# HITOMI.net
KiCad netlist of a schematic drawn in EAGLE
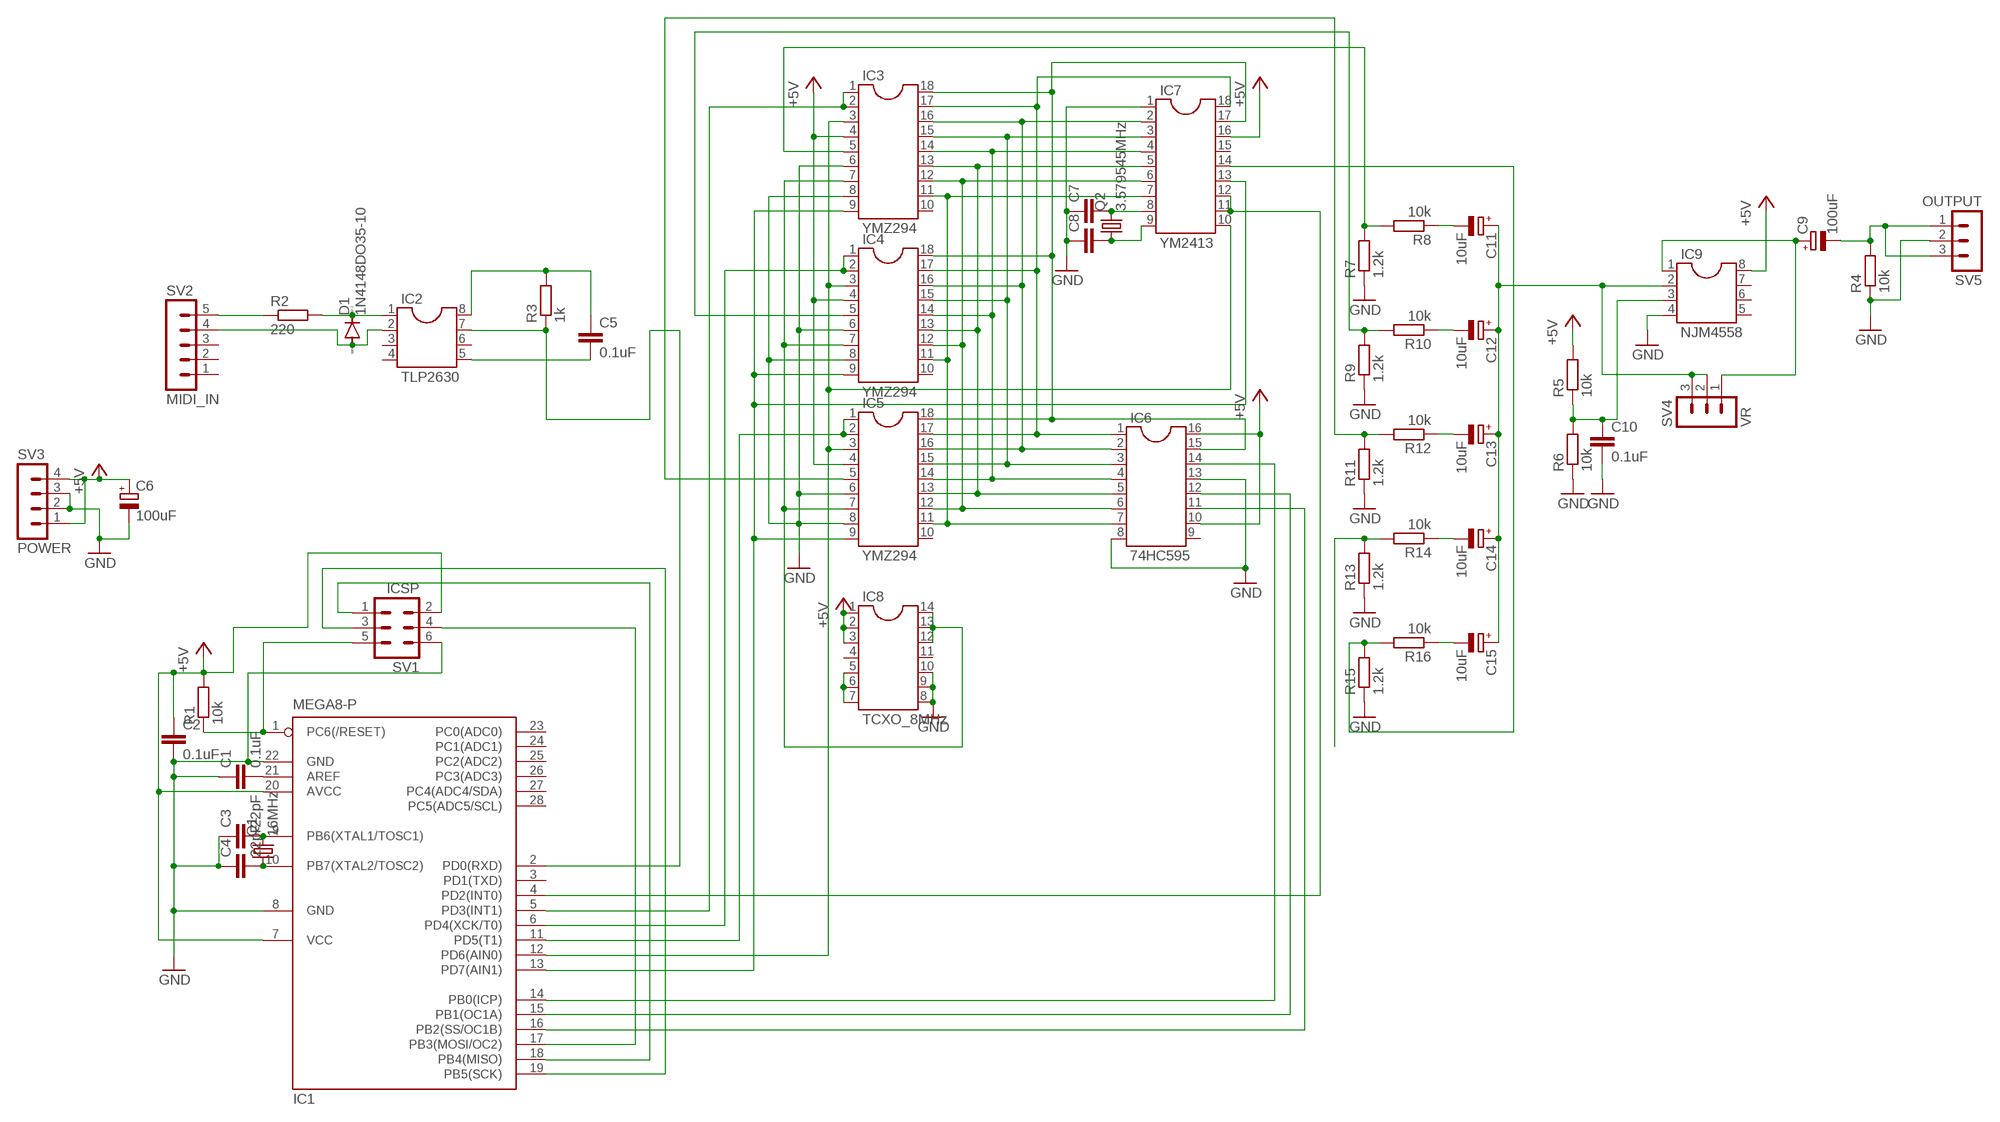
[diagram p0: schematic, sheet 1]

(export (version "E")
  (design (tool "Eeschema 10.0.6"))
  (components
    (comp (ref "C1")
      (value "0.1uF")
      (footprint "eagle-import:C050-025X075")
      (libsource (lib "eagle-import") (part "C-EU050-025X075"))
    )
    (comp (ref "C2")
      (value "0.1uF")
      (footprint "eagle-import:C050-025X075")
      (libsource (lib "eagle-import") (part "C-EU050-025X075"))
    )
    (comp (ref "C3")
      (value "22pF")
      (footprint "eagle-import:C050-025X075")
      (libsource (lib "eagle-import") (part "C-EU050-025X075"))
    )
    (comp (ref "C4")
      (value "22pF")
      (footprint "eagle-import:C050-025X075")
      (libsource (lib "eagle-import") (part "C-EU050-025X075"))
    )
    (comp (ref "C5")
      (value "0.1uF")
      (footprint "eagle-import:C050-025X075")
      (libsource (lib "eagle-import") (part "C-EU050-025X075"))
    )
    (comp (ref "C6")
      (value "100uF")
      (footprint "eagle-import:E2,5-7")
      (libsource (lib "eagle-import") (part "CPOL-EUE2.5-7"))
    )
    (comp (ref "C7")
      (value "C-EU050-025X075")
      (footprint "eagle-import:C050-025X075")
      (libsource (lib "eagle-import") (part "C-EU050-025X075"))
    )
    (comp (ref "C8")
      (value "C-EU050-025X075")
      (footprint "eagle-import:C050-025X075")
      (libsource (lib "eagle-import") (part "C-EU050-025X075"))
    )
    (comp (ref "C9")
      (value "100uF")
      (footprint "eagle-import:E2,5-7")
      (libsource (lib "eagle-import") (part "CPOL-EUE2.5-7"))
    )
    (comp (ref "C10")
      (value "0.1uF")
      (footprint "eagle-import:C050-025X075")
      (libsource (lib "eagle-import") (part "C-EU050-025X075"))
    )
    (comp (ref "C11")
      (value "10uF")
      (footprint "eagle-import:E2,5-7")
      (libsource (lib "eagle-import") (part "CPOL-EUE2.5-7"))
    )
    (comp (ref "C12")
      (value "10uF")
      (footprint "eagle-import:E2,5-7")
      (libsource (lib "eagle-import") (part "CPOL-EUE2.5-7"))
    )
    (comp (ref "C13")
      (value "10uF")
      (footprint "eagle-import:E2,5-7")
      (libsource (lib "eagle-import") (part "CPOL-EUE2.5-7"))
    )
    (comp (ref "C14")
      (value "10uF")
      (footprint "eagle-import:E2,5-7")
      (libsource (lib "eagle-import") (part "CPOL-EUE2.5-7"))
    )
    (comp (ref "C15")
      (value "10uF")
      (footprint "eagle-import:E2,5-7")
      (libsource (lib "eagle-import") (part "CPOL-EUE2.5-7"))
    )
    (comp (ref "D1")
      (value "1N4148DO35-10")
      (footprint "eagle-import:DO35-10")
      (libsource (lib "eagle-import") (part "1N4148DO35-10"))
    )
    (comp (ref "IC1")
      (value "MEGA8-P")
      (footprint "eagle-import:DIL28-3")
      (libsource (lib "eagle-import") (part "MEGA8-P"))
    )
    (comp (ref "IC2")
      (value "TLP2630")
      (footprint "eagle-import:DIL08")
      (libsource (lib "eagle-import") (part "DIL8"))
    )
    (comp (ref "IC3")
      (value "YMZ294")
      (footprint "eagle-import:SOCKET-18")
      (libsource (lib "eagle-import") (part "DIL18S"))
    )
    (comp (ref "IC4")
      (value "YMZ294")
      (footprint "eagle-import:SOCKET-18")
      (libsource (lib "eagle-import") (part "DIL18S"))
    )
    (comp (ref "IC5")
      (value "YMZ294")
      (footprint "eagle-import:SOCKET-18")
      (libsource (lib "eagle-import") (part "DIL18S"))
    )
    (comp (ref "IC6")
      (value "74HC595")
      (footprint "eagle-import:SOCKET-16")
      (libsource (lib "eagle-import") (part "DIL16S"))
    )
    (comp (ref "IC7")
      (value "YM2413")
      (footprint "eagle-import:SOCKET-18")
      (libsource (lib "eagle-import") (part "DIL18S"))
    )
    (comp (ref "IC8")
      (value "TCXO_8MHz")
      (footprint "eagle-import:DIL14")
      (libsource (lib "eagle-import") (part "DIL14"))
    )
    (comp (ref "IC9")
      (value "NJM4558")
      (footprint "eagle-import:DIL08")
      (libsource (lib "eagle-import") (part "DIL8"))
    )
    (comp (ref "Q1")
      (value "16MHz")
      (footprint "eagle-import:HC49_S")
      (libsource (lib "eagle-import") (part "CRYSTALHC49S"))
    )
    (comp (ref "Q2")
      (value "3.579545MHz")
      (footprint "eagle-import:HC49_S")
      (libsource (lib "eagle-import") (part "CRYSTALHC49S"))
    )
    (comp (ref "R1")
      (value "10k")
      (footprint "eagle-import:0207_10")
      (libsource (lib "eagle-import") (part "R-EU_0207/10"))
    )
    (comp (ref "R2")
      (value "220")
      (footprint "eagle-import:0207_10")
      (libsource (lib "eagle-import") (part "R-EU_0207/10"))
    )
    (comp (ref "R3")
      (value "1k")
      (footprint "eagle-import:0207_10")
      (libsource (lib "eagle-import") (part "R-EU_0207/10"))
    )
    (comp (ref "R4")
      (value "10k")
      (footprint "eagle-import:0207_10")
      (libsource (lib "eagle-import") (part "R-EU_0207/10"))
    )
    (comp (ref "R5")
      (value "10k")
      (footprint "eagle-import:0207_10")
      (libsource (lib "eagle-import") (part "R-EU_0207/10"))
    )
    (comp (ref "R6")
      (value "10k")
      (footprint "eagle-import:0207_10")
      (libsource (lib "eagle-import") (part "R-EU_0207/10"))
    )
    (comp (ref "R7")
      (value "1.2k")
      (footprint "eagle-import:0207_10")
      (libsource (lib "eagle-import") (part "R-EU_0207/10"))
    )
    (comp (ref "R8")
      (value "10k")
      (footprint "eagle-import:0207_10")
      (libsource (lib "eagle-import") (part "R-EU_0207/10"))
    )
    (comp (ref "R9")
      (value "1.2k")
      (footprint "eagle-import:0207_10")
      (libsource (lib "eagle-import") (part "R-EU_0207/10"))
    )
    (comp (ref "R10")
      (value "10k")
      (footprint "eagle-import:0207_10")
      (libsource (lib "eagle-import") (part "R-EU_0207/10"))
    )
    (comp (ref "R11")
      (value "1.2k")
      (footprint "eagle-import:0207_10")
      (libsource (lib "eagle-import") (part "R-EU_0207/10"))
    )
    (comp (ref "R12")
      (value "10k")
      (footprint "eagle-import:0207_10")
      (libsource (lib "eagle-import") (part "R-EU_0207/10"))
    )
    (comp (ref "R13")
      (value "1.2k")
      (footprint "eagle-import:0207_10")
      (libsource (lib "eagle-import") (part "R-EU_0207/10"))
    )
    (comp (ref "R14")
      (value "10k")
      (footprint "eagle-import:0207_10")
      (libsource (lib "eagle-import") (part "R-EU_0207/10"))
    )
    (comp (ref "R15")
      (value "1.2k")
      (footprint "eagle-import:0207_10")
      (libsource (lib "eagle-import") (part "R-EU_0207/10"))
    )
    (comp (ref "R16")
      (value "10k")
      (footprint "eagle-import:0207_10")
      (libsource (lib "eagle-import") (part "R-EU_0207/10"))
    )
    (comp (ref "SV1")
      (value "ICSP")
      (footprint "eagle-import:MA03-2")
      (libsource (lib "eagle-import") (part "MA03-2"))
    )
    (comp (ref "SV2")
      (value "MIDI_IN")
      (footprint "eagle-import:MA05-1")
      (libsource (lib "eagle-import") (part "MA05-1"))
    )
    (comp (ref "SV3")
      (value "POWER")
      (footprint "eagle-import:MA04-1")
      (libsource (lib "eagle-import") (part "MA04-1"))
    )
    (comp (ref "SV4")
      (value "VR")
      (footprint "eagle-import:MA03-1")
      (libsource (lib "eagle-import") (part "MA03-1"))
    )
    (comp (ref "SV5")
      (value "OUTPUT")
      (footprint "eagle-import:MA03-1")
      (libsource (lib "eagle-import") (part "MA03-1"))
    )
  )
  (nets
    (net (code "1") (name "+5V") (class "Default")
      (node (ref "C2") (pin "1") (pinfunction "1_1") (pintype "passive"))
      (node (ref "C6") (pin "+") (pinfunction "+_+") (pintype "passive"))
      (node (ref "IC1") (pin "20") (pinfunction "AVCC_20") (pintype "power_in"))
      (node (ref "IC1") (pin "7") (pinfunction "VCC_7") (pintype "power_in"))
      (node (ref "IC3") (pin "4") (pinfunction "4_4") (pintype "passive"))
      (node (ref "IC4") (pin "4") (pinfunction "4_4") (pintype "passive"))
      (node (ref "IC5") (pin "4") (pinfunction "4_4") (pintype "passive"))
      (node (ref "IC6") (pin "10") (pinfunction "10_10") (pintype "passive"))
      (node (ref "IC6") (pin "16") (pinfunction "16_16") (pintype "passive"))
      (node (ref "IC7") (pin "16") (pinfunction "16_16") (pintype "passive"))
      (node (ref "IC8") (pin "1") (pinfunction "1_1") (pintype "passive"))
      (node (ref "IC8") (pin "2") (pinfunction "2_2") (pintype "passive"))
      (node (ref "IC8") (pin "3") (pinfunction "3_3") (pintype "passive"))
      (node (ref "IC9") (pin "8") (pinfunction "8_8") (pintype "passive"))
      (node (ref "R1") (pin "2") (pinfunction "2_2") (pintype "passive"))
      (node (ref "R5") (pin "2") (pinfunction "2_2") (pintype "passive"))
      (node (ref "SV1") (pin "2") (pinfunction "2_2") (pintype "passive"))
      (node (ref "SV3") (pin "1") (pinfunction "1_1") (pintype "passive"))
      (node (ref "SV3") (pin "4") (pinfunction "4_4") (pintype "passive"))
    )
    (net (code "2") (name "GND") (class "Default")
      (node (ref "C1") (pin "1") (pinfunction "1_1") (pintype "passive"))
      (node (ref "C10") (pin "2") (pinfunction "2_2") (pintype "passive"))
      (node (ref "C2") (pin "2") (pinfunction "2_2") (pintype "passive"))
      (node (ref "C3") (pin "1") (pinfunction "1_1") (pintype "passive"))
      (node (ref "C4") (pin "1") (pinfunction "1_1") (pintype "passive"))
      (node (ref "C6") (pin "-") (pinfunction "-_-") (pintype "passive"))
      (node (ref "C7") (pin "1") (pinfunction "1_1") (pintype "passive"))
      (node (ref "C8") (pin "1") (pinfunction "1_1") (pintype "passive"))
      (node (ref "IC1") (pin "22") (pinfunction "GND_22") (pintype "power_in"))
      (node (ref "IC1") (pin "8") (pinfunction "GND_8") (pintype "power_in"))
      (node (ref "IC3") (pin "6") (pinfunction "6_6") (pintype "passive"))
      (node (ref "IC3") (pin "8") (pinfunction "8_8") (pintype "passive"))
      (node (ref "IC4") (pin "6") (pinfunction "6_6") (pintype "passive"))
      (node (ref "IC4") (pin "8") (pinfunction "8_8") (pintype "passive"))
      (node (ref "IC5") (pin "6") (pinfunction "6_6") (pintype "passive"))
      (node (ref "IC5") (pin "8") (pinfunction "8_8") (pintype "passive"))
      (node (ref "IC6") (pin "13") (pinfunction "13_13") (pintype "passive"))
      (node (ref "IC6") (pin "8") (pinfunction "8_8") (pintype "passive"))
      (node (ref "IC7") (pin "1") (pinfunction "1_1") (pintype "passive"))
      (node (ref "IC8") (pin "10") (pinfunction "10_10") (pintype "passive"))
      (node (ref "IC8") (pin "8") (pinfunction "8_8") (pintype "passive"))
      (node (ref "IC8") (pin "9") (pinfunction "9_9") (pintype "passive"))
      (node (ref "IC9") (pin "4") (pinfunction "4_4") (pintype "passive"))
      (node (ref "R11") (pin "1") (pinfunction "1_1") (pintype "passive"))
      (node (ref "R13") (pin "1") (pinfunction "1_1") (pintype "passive"))
      (node (ref "R15") (pin "1") (pinfunction "1_1") (pintype "passive"))
      (node (ref "R4") (pin "1") (pinfunction "1_1") (pintype "passive"))
      (node (ref "R6") (pin "1") (pinfunction "1_1") (pintype "passive"))
      (node (ref "R7") (pin "1") (pinfunction "1_1") (pintype "passive"))
      (node (ref "R9") (pin "1") (pinfunction "1_1") (pintype "passive"))
      (node (ref "SV1") (pin "6") (pinfunction "6_6") (pintype "passive"))
      (node (ref "SV3") (pin "2") (pinfunction "2_2") (pintype "passive"))
      (node (ref "SV3") (pin "3") (pinfunction "3_3") (pintype "passive"))
      (node (ref "SV5") (pin "2") (pinfunction "2_2") (pintype "passive"))
    )
    (net (code "3") (name "Net-(C5-Pad1)") (class "Default")
      (node (ref "C5") (pin "1") (pinfunction "1_1") (pintype "passive"))
      (node (ref "IC2") (pin "8") (pinfunction "8_8") (pintype "passive"))
      (node (ref "R3") (pin "2") (pinfunction "2_2") (pintype "passive"))
    )
    (net (code "4") (name "Net-(C5-Pad2)") (class "Default")
      (node (ref "C5") (pin "2") (pinfunction "2_2") (pintype "passive"))
      (node (ref "IC2") (pin "5") (pinfunction "5_5") (pintype "passive"))
    )
    (net (code "5") (name "Net-(C7-Pad2)") (class "Default")
      (node (ref "C7") (pin "2") (pinfunction "2_2") (pintype "passive"))
      (node (ref "IC7") (pin "8") (pinfunction "8_8") (pintype "passive"))
      (node (ref "Q2") (pin "2") (pinfunction "2_2") (pintype "passive"))
    )
    (net (code "6") (name "Net-(C8-Pad2)") (class "Default")
      (node (ref "C8") (pin "2") (pinfunction "2_2") (pintype "passive"))
      (node (ref "IC7") (pin "9") (pinfunction "9_9") (pintype "passive"))
      (node (ref "Q2") (pin "1") (pinfunction "1_1") (pintype "passive"))
    )
    (net (code "7") (name "Net-(C9-Pad+)") (class "Default")
      (node (ref "C9") (pin "+") (pinfunction "+_+") (pintype "passive"))
      (node (ref "IC9") (pin "1") (pinfunction "1_1") (pintype "passive"))
      (node (ref "SV4") (pin "1") (pinfunction "1_1") (pintype "passive"))
    )
    (net (code "8") (name "Net-(C9-Pad-)") (class "Default")
      (node (ref "C9") (pin "-") (pinfunction "-_-") (pintype "passive"))
      (node (ref "R4") (pin "2") (pinfunction "2_2") (pintype "passive"))
      (node (ref "SV5") (pin "1") (pinfunction "1_1") (pintype "passive"))
      (node (ref "SV5") (pin "3") (pinfunction "3_3") (pintype "passive"))
    )
    (net (code "9") (name "Net-(C10-Pad1)") (class "Default")
      (node (ref "C10") (pin "1") (pinfunction "1_1") (pintype "passive"))
      (node (ref "IC9") (pin "3") (pinfunction "3_3") (pintype "passive"))
      (node (ref "R5") (pin "1") (pinfunction "1_1") (pintype "passive"))
      (node (ref "R6") (pin "2") (pinfunction "2_2") (pintype "passive"))
    )
    (net (code "10") (name "Net-(C11-Pad+)") (class "Default")
      (node (ref "C11") (pin "+") (pinfunction "+_+") (pintype "passive"))
      (node (ref "C12") (pin "+") (pinfunction "+_+") (pintype "passive"))
      (node (ref "C13") (pin "+") (pinfunction "+_+") (pintype "passive"))
      (node (ref "C14") (pin "+") (pinfunction "+_+") (pintype "passive"))
      (node (ref "C15") (pin "+") (pinfunction "+_+") (pintype "passive"))
      (node (ref "IC9") (pin "2") (pinfunction "2_2") (pintype "passive"))
      (node (ref "SV4") (pin "2") (pinfunction "2_2") (pintype "passive"))
      (node (ref "SV4") (pin "3") (pinfunction "3_3") (pintype "passive"))
    )
    (net (code "11") (name "Net-(C11-Pad-)") (class "Default")
      (node (ref "C11") (pin "-") (pinfunction "-_-") (pintype "passive"))
      (node (ref "R8") (pin "1") (pinfunction "1_1") (pintype "passive"))
    )
    (net (code "12") (name "Net-(C12-Pad-)") (class "Default")
      (node (ref "C12") (pin "-") (pinfunction "-_-") (pintype "passive"))
      (node (ref "R10") (pin "1") (pinfunction "1_1") (pintype "passive"))
    )
    (net (code "13") (name "Net-(C13-Pad-)") (class "Default")
      (node (ref "C13") (pin "-") (pinfunction "-_-") (pintype "passive"))
      (node (ref "R12") (pin "1") (pinfunction "1_1") (pintype "passive"))
    )
    (net (code "14") (name "Net-(C14-Pad-)") (class "Default")
      (node (ref "C14") (pin "-") (pinfunction "-_-") (pintype "passive"))
      (node (ref "R14") (pin "1") (pinfunction "1_1") (pintype "passive"))
    )
    (net (code "15") (name "Net-(C15-Pad-)") (class "Default")
      (node (ref "C15") (pin "-") (pinfunction "-_-") (pintype "passive"))
      (node (ref "R16") (pin "1") (pinfunction "1_1") (pintype "passive"))
    )
    (net (code "16") (name "Net-(D1-PadA)") (class "Default")
      (node (ref "D1") (pin "A") (pinfunction "A_A") (pintype "passive"))
      (node (ref "IC2") (pin "2") (pinfunction "2_2") (pintype "passive"))
      (node (ref "SV2") (pin "4") (pinfunction "4_4") (pintype "passive"))
    )
    (net (code "17") (name "Net-(D1-PadC)") (class "Default")
      (node (ref "D1") (pin "C") (pinfunction "C_C") (pintype "passive"))
      (node (ref "IC2") (pin "1") (pinfunction "1_1") (pintype "passive"))
      (node (ref "R2") (pin "2") (pinfunction "2_2") (pintype "passive"))
    )
    (net (code "18") (name "Net-(IC1-AREF)") (class "Default")
      (node (ref "C1") (pin "2") (pinfunction "2_2") (pintype "passive"))
      (node (ref "IC1") (pin "21") (pinfunction "AREF_21") (pintype "passive"))
    )
    (net (code "19") (name "Net-(IC1-PB0(ICP))") (class "Default")
      (node (ref "IC1") (pin "14") (pinfunction "PB0(ICP)_14") (pintype "bidirectional"))
      (node (ref "IC6") (pin "14") (pinfunction "14_14") (pintype "passive"))
    )
    (net (code "20") (name "Net-(IC1-PB1(OC1A))") (class "Default")
      (node (ref "IC1") (pin "15") (pinfunction "PB1(OC1A)_15") (pintype "bidirectional"))
      (node (ref "IC6") (pin "12") (pinfunction "12_12") (pintype "passive"))
    )
    (net (code "21") (name "Net-(IC1-PB2(SS{slash}OC1B))") (class "Default")
      (node (ref "IC1") (pin "16") (pinfunction "PB2(SS/OC1B)_16") (pintype "bidirectional"))
      (node (ref "IC6") (pin "11") (pinfunction "11_11") (pintype "passive"))
    )
    (net (code "22") (name "Net-(IC1-PB3(MOSI{slash}OC2))") (class "Default")
      (node (ref "IC1") (pin "17") (pinfunction "PB3(MOSI/OC2)_17") (pintype "bidirectional"))
      (node (ref "SV1") (pin "4") (pinfunction "4_4") (pintype "passive"))
    )
    (net (code "23") (name "Net-(IC1-PB4(MISO))") (class "Default")
      (node (ref "IC1") (pin "18") (pinfunction "PB4(MISO)_18") (pintype "bidirectional"))
      (node (ref "SV1") (pin "1") (pinfunction "1_1") (pintype "passive"))
    )
    (net (code "24") (name "Net-(IC1-PB5(SCK))") (class "Default")
      (node (ref "IC1") (pin "19") (pinfunction "PB5(SCK)_19") (pintype "bidirectional"))
      (node (ref "SV1") (pin "3") (pinfunction "3_3") (pintype "passive"))
    )
    (net (code "25") (name "Net-(IC1-PB6(XTAL1{slash}TOSC1))") (class "Default")
      (node (ref "C3") (pin "2") (pinfunction "2_2") (pintype "passive"))
      (node (ref "IC1") (pin "9") (pinfunction "PB6(XTAL1/TOSC1)_9") (pintype "bidirectional"))
      (node (ref "Q1") (pin "2") (pinfunction "2_2") (pintype "passive"))
    )
    (net (code "26") (name "Net-(IC1-PB7(XTAL2{slash}TOSC2))") (class "Default")
      (node (ref "C4") (pin "2") (pinfunction "2_2") (pintype "passive"))
      (node (ref "IC1") (pin "10") (pinfunction "PB7(XTAL2/TOSC2)_10") (pintype "bidirectional"))
      (node (ref "Q1") (pin "1") (pinfunction "1_1") (pintype "passive"))
    )
    (net (code "27") (name "Net-(IC1-PC6({slash}RESET))") (class "Default")
      (node (ref "IC1") (pin "1") (pinfunction "PC6(/RESET)_1") (pintype "bidirectional"))
      (node (ref "R1") (pin "1") (pinfunction "1_1") (pintype "passive"))
      (node (ref "SV1") (pin "5") (pinfunction "5_5") (pintype "passive"))
    )
    (net (code "28") (name "Net-(IC1-PD0(RXD))") (class "Default")
      (node (ref "IC1") (pin "2") (pinfunction "PD0(RXD)_2") (pintype "bidirectional"))
      (node (ref "IC2") (pin "7") (pinfunction "7_7") (pintype "passive"))
      (node (ref "R3") (pin "1") (pinfunction "1_1") (pintype "passive"))
    )
    (net (code "29") (name "Net-(IC1-PD2(INT0))") (class "Default")
      (node (ref "IC1") (pin "4") (pinfunction "PD2(INT0)_4") (pintype "bidirectional"))
      (node (ref "IC7") (pin "11") (pinfunction "11_11") (pintype "passive"))
      (node (ref "IC7") (pin "12") (pinfunction "12_12") (pintype "passive"))
    )
    (net (code "30") (name "Net-(IC1-PD3(INT1))") (class "Default")
      (node (ref "IC1") (pin "5") (pinfunction "PD3(INT1)_5") (pintype "bidirectional"))
      (node (ref "IC3") (pin "1") (pinfunction "1_1") (pintype "passive"))
      (node (ref "IC3") (pin "2") (pinfunction "2_2") (pintype "passive"))
    )
    (net (code "31") (name "Net-(IC1-PD4(XCK{slash}T0))") (class "Default")
      (node (ref "IC1") (pin "6") (pinfunction "PD4(XCK/T0)_6") (pintype "bidirectional"))
      (node (ref "IC4") (pin "1") (pinfunction "1_1") (pintype "passive"))
      (node (ref "IC4") (pin "2") (pinfunction "2_2") (pintype "passive"))
    )
    (net (code "32") (name "Net-(IC1-PD5(T1))") (class "Default")
      (node (ref "IC1") (pin "11") (pinfunction "PD5(T1)_11") (pintype "bidirectional"))
      (node (ref "IC5") (pin "1") (pinfunction "1_1") (pintype "passive"))
      (node (ref "IC5") (pin "2") (pinfunction "2_2") (pintype "passive"))
    )
    (net (code "33") (name "Net-(IC1-PD6(AIN0))") (class "Default")
      (node (ref "IC1") (pin "12") (pinfunction "PD6(AIN0)_12") (pintype "bidirectional"))
      (node (ref "IC3") (pin "3") (pinfunction "3_3") (pintype "passive"))
      (node (ref "IC4") (pin "3") (pinfunction "3_3") (pintype "passive"))
      (node (ref "IC5") (pin "3") (pinfunction "3_3") (pintype "passive"))
      (node (ref "IC7") (pin "10") (pinfunction "10_10") (pintype "passive"))
    )
    (net (code "34") (name "Net-(IC1-PD7(AIN1))") (class "Default")
      (node (ref "IC1") (pin "13") (pinfunction "PD7(AIN1)_13") (pintype "bidirectional"))
      (node (ref "IC3") (pin "9") (pinfunction "9_9") (pintype "passive"))
      (node (ref "IC4") (pin "9") (pinfunction "9_9") (pintype "passive"))
      (node (ref "IC5") (pin "9") (pinfunction "9_9") (pintype "passive"))
      (node (ref "IC7") (pin "13") (pinfunction "13_13") (pintype "passive"))
    )
    (net (code "35") (name "Net-(IC3-Pad5)") (class "Default")
      (node (ref "IC3") (pin "5") (pinfunction "5_5") (pintype "passive"))
      (node (ref "R7") (pin "2") (pinfunction "2_2") (pintype "passive"))
      (node (ref "R8") (pin "2") (pinfunction "2_2") (pintype "passive"))
    )
    (net (code "36") (name "Net-(IC3-Pad7)") (class "Default")
      (node (ref "IC3") (pin "7") (pinfunction "7_7") (pintype "passive"))
      (node (ref "IC4") (pin "7") (pinfunction "7_7") (pintype "passive"))
      (node (ref "IC5") (pin "7") (pinfunction "7_7") (pintype "passive"))
      (node (ref "IC8") (pin "12") (pinfunction "12_12") (pintype "passive"))
      (node (ref "IC8") (pin "13") (pinfunction "13_13") (pintype "passive"))
      (node (ref "IC8") (pin "14") (pinfunction "14_14") (pintype "passive"))
    )
    (net (code "37") (name "Net-(IC3-Pad11)") (class "Default")
      (node (ref "IC3") (pin "11") (pinfunction "11_11") (pintype "passive"))
      (node (ref "IC4") (pin "11") (pinfunction "11_11") (pintype "passive"))
      (node (ref "IC5") (pin "11") (pinfunction "11_11") (pintype "passive"))
      (node (ref "IC6") (pin "7") (pinfunction "7_7") (pintype "passive"))
      (node (ref "IC7") (pin "7") (pinfunction "7_7") (pintype "passive"))
    )
    (net (code "38") (name "Net-(IC3-Pad12)") (class "Default")
      (node (ref "IC3") (pin "12") (pinfunction "12_12") (pintype "passive"))
      (node (ref "IC4") (pin "12") (pinfunction "12_12") (pintype "passive"))
      (node (ref "IC5") (pin "12") (pinfunction "12_12") (pintype "passive"))
      (node (ref "IC6") (pin "6") (pinfunction "6_6") (pintype "passive"))
      (node (ref "IC7") (pin "6") (pinfunction "6_6") (pintype "passive"))
    )
    (net (code "39") (name "Net-(IC3-Pad13)") (class "Default")
      (node (ref "IC3") (pin "13") (pinfunction "13_13") (pintype "passive"))
      (node (ref "IC4") (pin "13") (pinfunction "13_13") (pintype "passive"))
      (node (ref "IC5") (pin "13") (pinfunction "13_13") (pintype "passive"))
      (node (ref "IC6") (pin "5") (pinfunction "5_5") (pintype "passive"))
      (node (ref "IC7") (pin "5") (pinfunction "5_5") (pintype "passive"))
    )
    (net (code "40") (name "Net-(IC3-Pad14)") (class "Default")
      (node (ref "IC3") (pin "14") (pinfunction "14_14") (pintype "passive"))
      (node (ref "IC4") (pin "14") (pinfunction "14_14") (pintype "passive"))
      (node (ref "IC5") (pin "14") (pinfunction "14_14") (pintype "passive"))
      (node (ref "IC6") (pin "4") (pinfunction "4_4") (pintype "passive"))
      (node (ref "IC7") (pin "4") (pinfunction "4_4") (pintype "passive"))
    )
    (net (code "41") (name "Net-(IC3-Pad15)") (class "Default")
      (node (ref "IC3") (pin "15") (pinfunction "15_15") (pintype "passive"))
      (node (ref "IC4") (pin "15") (pinfunction "15_15") (pintype "passive"))
      (node (ref "IC5") (pin "15") (pinfunction "15_15") (pintype "passive"))
      (node (ref "IC6") (pin "3") (pinfunction "3_3") (pintype "passive"))
      (node (ref "IC7") (pin "3") (pinfunction "3_3") (pintype "passive"))
    )
    (net (code "42") (name "Net-(IC3-Pad16)") (class "Default")
      (node (ref "IC3") (pin "16") (pinfunction "16_16") (pintype "passive"))
      (node (ref "IC4") (pin "16") (pinfunction "16_16") (pintype "passive"))
      (node (ref "IC5") (pin "16") (pinfunction "16_16") (pintype "passive"))
      (node (ref "IC6") (pin "2") (pinfunction "2_2") (pintype "passive"))
      (node (ref "IC7") (pin "2") (pinfunction "2_2") (pintype "passive"))
    )
    (net (code "43") (name "Net-(IC3-Pad17)") (class "Default")
      (node (ref "IC3") (pin "17") (pinfunction "17_17") (pintype "passive"))
      (node (ref "IC4") (pin "17") (pinfunction "17_17") (pintype "passive"))
      (node (ref "IC5") (pin "17") (pinfunction "17_17") (pintype "passive"))
      (node (ref "IC6") (pin "1") (pinfunction "1_1") (pintype "passive"))
      (node (ref "IC7") (pin "18") (pinfunction "18_18") (pintype "passive"))
    )
    (net (code "44") (name "Net-(IC3-Pad18)") (class "Default")
      (node (ref "IC3") (pin "18") (pinfunction "18_18") (pintype "passive"))
      (node (ref "IC4") (pin "18") (pinfunction "18_18") (pintype "passive"))
      (node (ref "IC5") (pin "18") (pinfunction "18_18") (pintype "passive"))
      (node (ref "IC6") (pin "15") (pinfunction "15_15") (pintype "passive"))
      (node (ref "IC7") (pin "17") (pinfunction "17_17") (pintype "passive"))
    )
    (net (code "45") (name "Net-(IC4-Pad5)") (class "Default")
      (node (ref "IC4") (pin "5") (pinfunction "5_5") (pintype "passive"))
      (node (ref "R10") (pin "2") (pinfunction "2_2") (pintype "passive"))
      (node (ref "R9") (pin "2") (pinfunction "2_2") (pintype "passive"))
    )
    (net (code "46") (name "Net-(IC5-Pad5)") (class "Default")
      (node (ref "IC5") (pin "5") (pinfunction "5_5") (pintype "passive"))
      (node (ref "R11") (pin "2") (pinfunction "2_2") (pintype "passive"))
      (node (ref "R12") (pin "2") (pinfunction "2_2") (pintype "passive"))
    )
    (net (code "47") (name "Net-(IC7-Pad14)") (class "Default")
      (node (ref "IC7") (pin "14") (pinfunction "14_14") (pintype "passive"))
      (node (ref "R15") (pin "2") (pinfunction "2_2") (pintype "passive"))
      (node (ref "R16") (pin "2") (pinfunction "2_2") (pintype "passive"))
    )
    (net (code "48") (name "Net-(IC8-Pad5)") (class "Default")
      (node (ref "IC8") (pin "5") (pinfunction "5_5") (pintype "passive"))
      (node (ref "IC8") (pin "6") (pinfunction "6_6") (pintype "passive"))
      (node (ref "IC8") (pin "7") (pinfunction "7_7") (pintype "passive"))
    )
    (net (code "49") (name "Net-(R2-Pad1)") (class "Default")
      (node (ref "R2") (pin "1") (pinfunction "1_1") (pintype "passive"))
      (node (ref "SV2") (pin "5") (pinfunction "5_5") (pintype "passive"))
    )
    (net (code "50") (name "Net-(R13-Pad2)") (class "Default")
      (node (ref "R13") (pin "2") (pinfunction "2_2") (pintype "passive"))
      (node (ref "R14") (pin "2") (pinfunction "2_2") (pintype "passive"))
    )
    (net (code "51") (name "unconnected-(IC1-PC0(ADC0)-Pad23)") (class "Default")
      (node (ref "IC1") (pin "23") (pinfunction "PC0(ADC0)_23") (pintype "bidirectional"))
    )
    (net (code "52") (name "unconnected-(IC1-PC1(ADC1)-Pad24)") (class "Default")
      (node (ref "IC1") (pin "24") (pinfunction "PC1(ADC1)_24") (pintype "bidirectional"))
    )
    (net (code "53") (name "unconnected-(IC1-PC2(ADC2)-Pad25)") (class "Default")
      (node (ref "IC1") (pin "25") (pinfunction "PC2(ADC2)_25") (pintype "bidirectional"))
    )
    (net (code "54") (name "unconnected-(IC1-PC3(ADC3)-Pad26)") (class "Default")
      (node (ref "IC1") (pin "26") (pinfunction "PC3(ADC3)_26") (pintype "bidirectional"))
    )
    (net (code "55") (name "unconnected-(IC1-PC4(ADC4{slash}SDA)-Pad27)") (class "Default")
      (node (ref "IC1") (pin "27") (pinfunction "PC4(ADC4/SDA)_27") (pintype "bidirectional"))
    )
    (net (code "56") (name "unconnected-(IC1-PC5(ADC5{slash}SCL)-Pad28)") (class "Default")
      (node (ref "IC1") (pin "28") (pinfunction "PC5(ADC5/SCL)_28") (pintype "bidirectional"))
    )
    (net (code "57") (name "unconnected-(IC1-PD1(TXD)-Pad3)") (class "Default")
      (node (ref "IC1") (pin "3") (pinfunction "PD1(TXD)_3") (pintype "bidirectional"))
    )
    (net (code "58") (name "unconnected-(IC2-Pad3)") (class "Default")
      (node (ref "IC2") (pin "3") (pinfunction "3_3") (pintype "passive"))
    )
    (net (code "59") (name "unconnected-(IC2-Pad4)") (class "Default")
      (node (ref "IC2") (pin "4") (pinfunction "4_4") (pintype "passive"))
    )
    (net (code "60") (name "unconnected-(IC2-Pad6)") (class "Default")
      (node (ref "IC2") (pin "6") (pinfunction "6_6") (pintype "passive"))
    )
    (net (code "61") (name "unconnected-(IC3-Pad10)") (class "Default")
      (node (ref "IC3") (pin "10") (pinfunction "10_10") (pintype "passive"))
    )
    (net (code "62") (name "unconnected-(IC4-Pad10)") (class "Default")
      (node (ref "IC4") (pin "10") (pinfunction "10_10") (pintype "passive"))
    )
    (net (code "63") (name "unconnected-(IC5-Pad10)") (class "Default")
      (node (ref "IC5") (pin "10") (pinfunction "10_10") (pintype "passive"))
    )
    (net (code "64") (name "unconnected-(IC6-Pad9)") (class "Default")
      (node (ref "IC6") (pin "9") (pinfunction "9_9") (pintype "passive"))
    )
    (net (code "65") (name "unconnected-(IC7-Pad15)") (class "Default")
      (node (ref "IC7") (pin "15") (pinfunction "15_15") (pintype "passive"))
    )
    (net (code "66") (name "unconnected-(IC8-Pad4)") (class "Default")
      (node (ref "IC8") (pin "4") (pinfunction "4_4") (pintype "passive"))
    )
    (net (code "67") (name "unconnected-(IC8-Pad11)") (class "Default")
      (node (ref "IC8") (pin "11") (pinfunction "11_11") (pintype "passive"))
    )
    (net (code "68") (name "unconnected-(IC9-Pad5)") (class "Default")
      (node (ref "IC9") (pin "5") (pinfunction "5_5") (pintype "passive"))
    )
    (net (code "69") (name "unconnected-(IC9-Pad6)") (class "Default")
      (node (ref "IC9") (pin "6") (pinfunction "6_6") (pintype "passive"))
    )
    (net (code "70") (name "unconnected-(IC9-Pad7)") (class "Default")
      (node (ref "IC9") (pin "7") (pinfunction "7_7") (pintype "passive"))
    )
    (net (code "71") (name "unconnected-(SV2-Pad1)") (class "Default")
      (node (ref "SV2") (pin "1") (pinfunction "1_1") (pintype "passive"))
    )
    (net (code "72") (name "unconnected-(SV2-Pad2)") (class "Default")
      (node (ref "SV2") (pin "2") (pinfunction "2_2") (pintype "passive"))
    )
    (net (code "73") (name "unconnected-(SV2-Pad3)") (class "Default")
      (node (ref "SV2") (pin "3") (pinfunction "3_3") (pintype "passive"))
    )
  )
)
